# flowerfriend_rev6-nosma.net
KiCad netlist of a schematic drawn in EAGLE
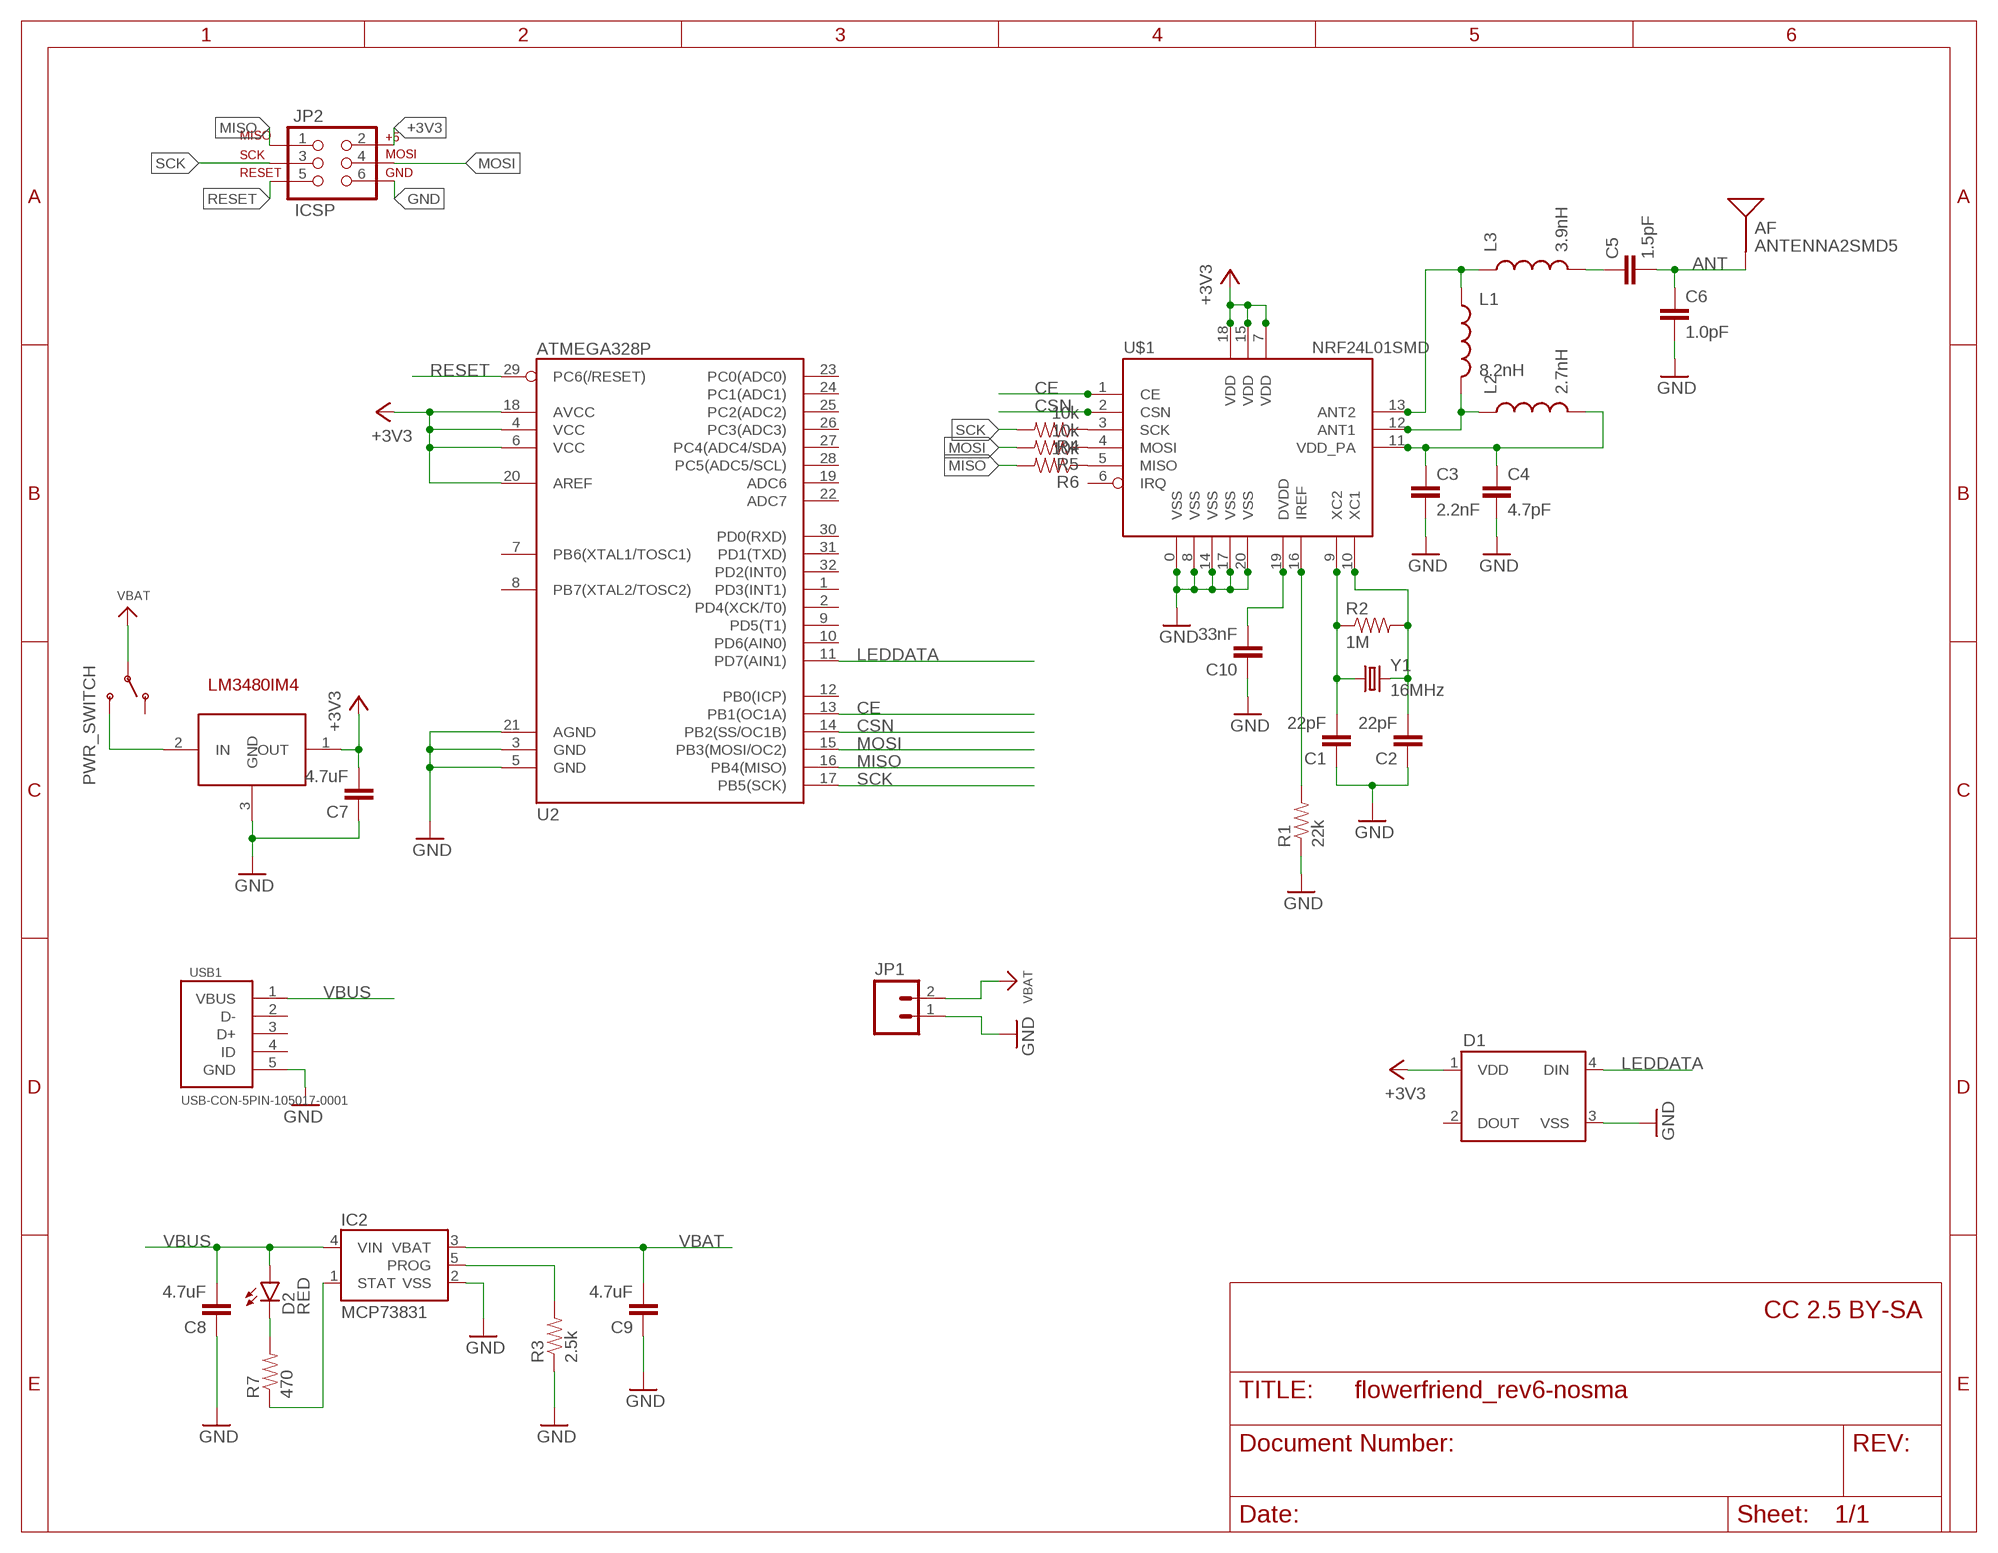
[diagram p0: schematic, sheet 1]

(export (version "E")
  (design (tool "Eeschema 10.0.6"))
  (components
    (comp (ref "AF")
      (value "ANTENNA2SMD5")
      (footprint "eagle-import:ANTENNA-CHIP5")
      (libsource (lib "eagle-import") (part "ANTENNA2SMD5"))
    )
    (comp (ref "C1")
      (value "22pF")
      (footprint "eagle-import:0805")
      (libsource (lib "eagle-import") (part "CAP0805"))
    )
    (comp (ref "C2")
      (value "22pF")
      (footprint "eagle-import:0805")
      (libsource (lib "eagle-import") (part "CAP0805"))
    )
    (comp (ref "C3")
      (value "2.2nF")
      (footprint "eagle-import:C0402")
      (libsource (lib "eagle-import") (part "CAP_C0402"))
    )
    (comp (ref "C4")
      (value "4.7pF")
      (footprint "eagle-import:C0402")
      (libsource (lib "eagle-import") (part "CAP_C0402"))
    )
    (comp (ref "C5")
      (value "1.5pF")
      (footprint "eagle-import:C0402")
      (libsource (lib "eagle-import") (part "CAP_C0402"))
    )
    (comp (ref "C6")
      (value "1.0pF")
      (footprint "eagle-import:C0402")
      (libsource (lib "eagle-import") (part "CAP_C0402"))
    )
    (comp (ref "C7")
      (value "4.7uF")
      (footprint "eagle-import:0805")
      (libsource (lib "eagle-import") (part "CAP0805"))
    )
    (comp (ref "C8")
      (value "4.7uF")
      (footprint "eagle-import:0805")
      (libsource (lib "eagle-import") (part "CAP0805"))
    )
    (comp (ref "C9")
      (value "4.7uF")
      (footprint "eagle-import:0805")
      (libsource (lib "eagle-import") (part "CAP0805"))
    )
    (comp (ref "C10")
      (value "33nF")
      (footprint "eagle-import:0805")
      (libsource (lib "eagle-import") (part "CAP0805"))
    )
    (comp (ref "D1")
      (value "WS2812B")
      (footprint "eagle-import:WS2812B")
      (libsource (lib "eagle-import") (part "WS2812B"))
    )
    (comp (ref "D2")
      (value "RED")
      (footprint "eagle-import:LED-0603")
      (libsource (lib "eagle-import") (part "LED-RED0603"))
    )
    (comp (ref "IC1")
      (value "LM3480IM4")
      (footprint "eagle-import:SOT23-3")
      (libsource (lib "eagle-import") (part "LM3480IM4"))
    )
    (comp (ref "IC2")
      (value "MCP73831")
      (footprint "eagle-import:SOT23-5")
      (libsource (lib "eagle-import") (part "MCP73831"))
    )
    (comp (ref "JP1")
      (value "M02PTH")
      (footprint "eagle-import:1X02")
      (libsource (lib "eagle-import") (part "M02PTH"))
    )
    (comp (ref "JP2")
      (value "ICSP")
      (footprint "eagle-import:2X3")
      (libsource (lib "eagle-import") (part "AVR_SPI_PRG_6PTH"))
    )
    (comp (ref "L1")
      (value "8.2nH")
      (footprint "eagle-import:C0402")
      (libsource (lib "eagle-import") (part "INDUCTOR0402"))
    )
    (comp (ref "L2")
      (value "2.7nH")
      (footprint "eagle-import:C0402")
      (libsource (lib "eagle-import") (part "INDUCTOR0402"))
    )
    (comp (ref "L3")
      (value "3.9nH")
      (footprint "eagle-import:C0402")
      (libsource (lib "eagle-import") (part "INDUCTOR0402"))
    )
    (comp (ref "PWR_SWITCH")
      (value "SWITCH_SPDT")
      (footprint "eagle-import:KPS-1290")
      (libsource (lib "eagle-import") (part "SWITCH_SPDT"))
    )
    (comp (ref "R1")
      (value "22k")
      (footprint "eagle-import:0805")
      (libsource (lib "eagle-import") (part "RESISTOR0805-RES"))
    )
    (comp (ref "R2")
      (value "1M")
      (footprint "eagle-import:0805")
      (libsource (lib "eagle-import") (part "RESISTOR0805-RES"))
    )
    (comp (ref "R3")
      (value "2.5k")
      (footprint "eagle-import:0805")
      (libsource (lib "eagle-import") (part "RESISTOR0805-RES"))
    )
    (comp (ref "R4")
      (value "10k")
      (footprint "eagle-import:0805")
      (libsource (lib "eagle-import") (part "RESISTOR0805-RES"))
    )
    (comp (ref "R5")
      (value "10k")
      (footprint "eagle-import:0805")
      (libsource (lib "eagle-import") (part "RESISTOR0805-RES"))
    )
    (comp (ref "R6")
      (value "10k")
      (footprint "eagle-import:0805")
      (libsource (lib "eagle-import") (part "RESISTOR0805-RES"))
    )
    (comp (ref "R7")
      (value "470")
      (footprint "eagle-import:0805")
      (libsource (lib "eagle-import") (part "RESISTOR0805-RES"))
    )
    (comp (ref "U$1")
      (value "NRF24L01SMD")
      (footprint "eagle-import:QFN20")
      (libsource (lib "eagle-import") (part "NRF24L01SMD"))
    )
    (comp (ref "U2")
      (value "ATMEGA328P")
      (footprint "eagle-import:TQFP32-08")
      (libsource (lib "eagle-import") (part "ATMEGA328_SMT"))
    )
    (comp (ref "USB1")
      (value "USB-CON-5PIN-105017-0001")
      (footprint "eagle-import:USB-MICRO-MOLEX-105017-0001")
      (libsource (lib "eagle-import") (part "USB-CON-5PIN-105017-0001"))
    )
    (comp (ref "Y1")
      (value "16MHz")
      (footprint "eagle-import:CRYSTAL-SMD-5X3")
      (libsource (lib "eagle-import") (part "CRYSTAL5X3"))
    )
  )
  (nets
    (net (code "1") (name "+3V3") (class "Default")
      (node (ref "C7") (pin "2") (pinfunction "2_2") (pintype "passive"))
      (node (ref "D1") (pin "1") (pinfunction "VDD_1") (pintype "power_in"))
      (node (ref "IC1") (pin "1") (pinfunction "OUT_1") (pintype "bidirectional"))
      (node (ref "JP2") (pin "2") (pinfunction "2_2") (pintype "passive"))
      (node (ref "U$1") (pin "15") (pinfunction "VDD_15") (pintype "power_in"))
      (node (ref "U$1") (pin "18") (pinfunction "VDD_18") (pintype "power_in"))
      (node (ref "U$1") (pin "7") (pinfunction "VDD_7") (pintype "power_in"))
      (node (ref "U2") (pin "18") (pinfunction "AVCC_18") (pintype "bidirectional"))
      (node (ref "U2") (pin "20") (pinfunction "AREF_20") (pintype "bidirectional"))
      (node (ref "U2") (pin "4") (pinfunction "VCC_4") (pintype "bidirectional"))
      (node (ref "U2") (pin "6") (pinfunction "VCC_6") (pintype "bidirectional"))
    )
    (net (code "2") (name "/ANT") (class "Default")
      (node (ref "AF") (pin "FEED") (pinfunction "SIGNAL_FEED") (pintype "bidirectional"))
      (node (ref "C5") (pin "2") (pinfunction "2_2") (pintype "passive"))
      (node (ref "C6") (pin "1") (pinfunction "1_1") (pintype "passive"))
    )
    (net (code "3") (name "/CE") (class "Default")
      (node (ref "U$1") (pin "1") (pinfunction "CE_1") (pintype "input"))
      (node (ref "U2") (pin "13") (pinfunction "PB1(OC1A)_13") (pintype "bidirectional"))
    )
    (net (code "4") (name "/CSN") (class "Default")
      (node (ref "U$1") (pin "2") (pinfunction "CSN_2") (pintype "input"))
      (node (ref "U2") (pin "14") (pinfunction "PB2(SS/OC1B)_14") (pintype "bidirectional"))
    )
    (net (code "5") (name "/LEDDATA") (class "Default")
      (node (ref "D1") (pin "4") (pinfunction "DIN_4") (pintype "input"))
      (node (ref "U2") (pin "11") (pinfunction "PD7(AIN1)_11") (pintype "bidirectional"))
    )
    (net (code "6") (name "/VBUS") (class "Default")
      (node (ref "C8") (pin "2") (pinfunction "2_2") (pintype "passive"))
      (node (ref "D2") (pin "A") (pinfunction "A_A") (pintype "passive"))
      (node (ref "IC2") (pin "4") (pinfunction "VIN_4") (pintype "power_in"))
      (node (ref "USB1") (pin "1") (pinfunction "VBUS_1") (pintype "power_in"))
    )
    (net (code "7") (name "GND") (class "Default")
      (node (ref "C1") (pin "1") (pinfunction "1_1") (pintype "passive"))
      (node (ref "C10") (pin "1") (pinfunction "1_1") (pintype "passive"))
      (node (ref "C2") (pin "1") (pinfunction "1_1") (pintype "passive"))
      (node (ref "C3") (pin "2") (pinfunction "2_2") (pintype "passive"))
      (node (ref "C4") (pin "2") (pinfunction "2_2") (pintype "passive"))
      (node (ref "C6") (pin "2") (pinfunction "2_2") (pintype "passive"))
      (node (ref "C7") (pin "1") (pinfunction "1_1") (pintype "passive"))
      (node (ref "C8") (pin "1") (pinfunction "1_1") (pintype "passive"))
      (node (ref "C9") (pin "1") (pinfunction "1_1") (pintype "passive"))
      (node (ref "D1") (pin "3") (pinfunction "VSS_3") (pintype "power_in"))
      (node (ref "IC1") (pin "3") (pinfunction "GND_3") (pintype "bidirectional"))
      (node (ref "IC2") (pin "2") (pinfunction "VSS_2") (pintype "power_in"))
      (node (ref "JP1") (pin "1") (pinfunction "1_1") (pintype "passive"))
      (node (ref "JP2") (pin "6") (pinfunction "6_6") (pintype "passive"))
      (node (ref "R1") (pin "1") (pinfunction "1_1") (pintype "passive"))
      (node (ref "R3") (pin "1") (pinfunction "1_1") (pintype "passive"))
      (node (ref "U$1") (pin "0") (pinfunction "VSS_0") (pintype "power_in"))
      (node (ref "U$1") (pin "14") (pinfunction "VSS_14") (pintype "power_in"))
      (node (ref "U$1") (pin "17") (pinfunction "VSS_17") (pintype "power_in"))
      (node (ref "U$1") (pin "20") (pinfunction "VSS_20") (pintype "power_in"))
      (node (ref "U$1") (pin "8") (pinfunction "VSS_8") (pintype "power_in"))
      (node (ref "U2") (pin "21") (pinfunction "AGND_21") (pintype "bidirectional"))
      (node (ref "U2") (pin "3") (pinfunction "GND_3") (pintype "bidirectional"))
      (node (ref "U2") (pin "5") (pinfunction "GND_5") (pintype "bidirectional"))
      (node (ref "USB1") (pin "5") (pinfunction "GND_5") (pintype "power_in"))
    )
    (net (code "8") (name "MISO") (class "Default")
      (node (ref "JP2") (pin "1") (pinfunction "1_1") (pintype "passive"))
      (node (ref "R6") (pin "2") (pinfunction "2_2") (pintype "passive"))
      (node (ref "U2") (pin "16") (pinfunction "PB4(MISO)_16") (pintype "bidirectional"))
    )
    (net (code "9") (name "MOSI") (class "Default")
      (node (ref "JP2") (pin "4") (pinfunction "4_4") (pintype "passive"))
      (node (ref "R5") (pin "2") (pinfunction "2_2") (pintype "passive"))
      (node (ref "U2") (pin "15") (pinfunction "PB3(MOSI/OC2)_15") (pintype "bidirectional"))
    )
    (net (code "10") (name "Net-(C5-Pad1)") (class "Default")
      (node (ref "C5") (pin "1") (pinfunction "1_1") (pintype "passive"))
      (node (ref "L3") (pin "2") (pinfunction "2_2") (pintype "passive"))
    )
    (net (code "11") (name "Net-(D2-PadC)") (class "Default")
      (node (ref "D2") (pin "C") (pinfunction "C_C") (pintype "passive"))
      (node (ref "R7") (pin "2") (pinfunction "2_2") (pintype "passive"))
    )
    (net (code "12") (name "Net-(IC1-IN)") (class "Default")
      (node (ref "IC1") (pin "2") (pinfunction "IN_2") (pintype "bidirectional"))
      (node (ref "PWR_SWITCH") (pin "S") (pinfunction "S_S") (pintype "passive"))
    )
    (net (code "13") (name "Net-(IC2-PROG)") (class "Default")
      (node (ref "IC2") (pin "5") (pinfunction "PROG_5") (pintype "input"))
      (node (ref "R3") (pin "2") (pinfunction "2_2") (pintype "passive"))
    )
    (net (code "14") (name "Net-(IC2-STAT)") (class "Default")
      (node (ref "IC2") (pin "1") (pinfunction "STAT_1") (pintype "output"))
      (node (ref "R7") (pin "1") (pinfunction "1_1") (pintype "passive"))
    )
    (net (code "15") (name "Net-(U$1-ANT1)") (class "Default")
      (node (ref "L1") (pin "2") (pinfunction "2_2") (pintype "passive"))
      (node (ref "L2") (pin "1") (pinfunction "1_1") (pintype "passive"))
      (node (ref "U$1") (pin "12") (pinfunction "ANT1_12") (pintype "output"))
    )
    (net (code "16") (name "Net-(U$1-ANT2)") (class "Default")
      (node (ref "L1") (pin "1") (pinfunction "1_1") (pintype "passive"))
      (node (ref "L3") (pin "1") (pinfunction "1_1") (pintype "passive"))
      (node (ref "U$1") (pin "13") (pinfunction "ANT2_13") (pintype "output"))
    )
    (net (code "17") (name "Net-(U$1-DVDD)") (class "Default")
      (node (ref "C10") (pin "2") (pinfunction "2_2") (pintype "passive"))
      (node (ref "U$1") (pin "19") (pinfunction "DVDD_19") (pintype "power_in"))
    )
    (net (code "18") (name "Net-(U$1-IREF)") (class "Default")
      (node (ref "R1") (pin "2") (pinfunction "2_2") (pintype "passive"))
      (node (ref "U$1") (pin "16") (pinfunction "IREF_16") (pintype "input"))
    )
    (net (code "19") (name "Net-(U$1-MISO)") (class "Default")
      (node (ref "R6") (pin "1") (pinfunction "1_1") (pintype "passive"))
      (node (ref "U$1") (pin "5") (pinfunction "MISO_5") (pintype "output"))
    )
    (net (code "20") (name "Net-(U$1-MOSI)") (class "Default")
      (node (ref "R5") (pin "1") (pinfunction "1_1") (pintype "passive"))
      (node (ref "U$1") (pin "4") (pinfunction "MOSI_4") (pintype "input"))
    )
    (net (code "21") (name "Net-(U$1-SCK)") (class "Default")
      (node (ref "R4") (pin "1") (pinfunction "1_1") (pintype "passive"))
      (node (ref "U$1") (pin "3") (pinfunction "SCK_3") (pintype "input"))
    )
    (net (code "22") (name "Net-(U$1-VDD_PA)") (class "Default")
      (node (ref "C3") (pin "1") (pinfunction "1_1") (pintype "passive"))
      (node (ref "C4") (pin "1") (pinfunction "1_1") (pintype "passive"))
      (node (ref "L2") (pin "2") (pinfunction "2_2") (pintype "passive"))
      (node (ref "U$1") (pin "11") (pinfunction "VDD_PA_11") (pintype "power_in"))
    )
    (net (code "23") (name "Net-(U$1-XC1)") (class "Default")
      (node (ref "C2") (pin "2") (pinfunction "2_2") (pintype "passive"))
      (node (ref "R2") (pin "2") (pinfunction "2_2") (pintype "passive"))
      (node (ref "U$1") (pin "10") (pinfunction "XC1_10") (pintype "input"))
      (node (ref "Y1") (pin "3") (pinfunction "2_3") (pintype "passive"))
    )
    (net (code "24") (name "Net-(U$1-XC2)") (class "Default")
      (node (ref "C1") (pin "2") (pinfunction "2_2") (pintype "passive"))
      (node (ref "R2") (pin "1") (pinfunction "1_1") (pintype "passive"))
      (node (ref "U$1") (pin "9") (pinfunction "XC2_9") (pintype "input"))
      (node (ref "Y1") (pin "1") (pinfunction "1_1") (pintype "passive"))
    )
    (net (code "25") (name "RESET") (class "Default")
      (node (ref "JP2") (pin "5") (pinfunction "5_5") (pintype "passive"))
      (node (ref "U2") (pin "29") (pinfunction "PC6(/RESET)_29") (pintype "bidirectional"))
    )
    (net (code "26") (name "SCK") (class "Default")
      (node (ref "JP2") (pin "3") (pinfunction "3_3") (pintype "passive"))
      (node (ref "R4") (pin "2") (pinfunction "2_2") (pintype "passive"))
      (node (ref "U2") (pin "17") (pinfunction "PB5(SCK)_17") (pintype "bidirectional"))
    )
    (net (code "27") (name "VBAT") (class "Default")
      (node (ref "C9") (pin "2") (pinfunction "2_2") (pintype "passive"))
      (node (ref "IC2") (pin "3") (pinfunction "VBAT_3") (pintype "power_in"))
      (node (ref "JP1") (pin "2") (pinfunction "2_2") (pintype "passive"))
      (node (ref "PWR_SWITCH") (pin "P") (pinfunction "P_P") (pintype "passive"))
    )
    (net (code "28") (name "unconnected-(D1-DOUT-Pad2)") (class "Default")
      (node (ref "D1") (pin "2") (pinfunction "DOUT_2") (pintype "output"))
    )
    (net (code "29") (name "unconnected-(PWR_SWITCH-PadO)") (class "Default")
      (node (ref "PWR_SWITCH") (pin "O") (pinfunction "O_O") (pintype "passive"))
    )
    (net (code "30") (name "unconnected-(U$1-IRQ-Pad6)") (class "Default")
      (node (ref "U$1") (pin "6") (pinfunction "IRQ_6") (pintype "output"))
    )
    (net (code "31") (name "unconnected-(U2-ADC6-Pad19)") (class "Default")
      (node (ref "U2") (pin "19") (pinfunction "ADC6_19") (pintype "bidirectional"))
    )
    (net (code "32") (name "unconnected-(U2-ADC7-Pad22)") (class "Default")
      (node (ref "U2") (pin "22") (pinfunction "ADC7_22") (pintype "bidirectional"))
    )
    (net (code "33") (name "unconnected-(U2-PB0(ICP)-Pad12)") (class "Default")
      (node (ref "U2") (pin "12") (pinfunction "PB0(ICP)_12") (pintype "bidirectional"))
    )
    (net (code "34") (name "unconnected-(U2-PB6(XTAL1{slash}TOSC1)-Pad7)") (class "Default")
      (node (ref "U2") (pin "7") (pinfunction "PB6(XTAL1/TOSC1)_7") (pintype "bidirectional"))
    )
    (net (code "35") (name "unconnected-(U2-PB7(XTAL2{slash}TOSC2)-Pad8)") (class "Default")
      (node (ref "U2") (pin "8") (pinfunction "PB7(XTAL2/TOSC2)_8") (pintype "bidirectional"))
    )
    (net (code "36") (name "unconnected-(U2-PC0(ADC0)-Pad23)") (class "Default")
      (node (ref "U2") (pin "23") (pinfunction "PC0(ADC0)_23") (pintype "bidirectional"))
    )
    (net (code "37") (name "unconnected-(U2-PC1(ADC1)-Pad24)") (class "Default")
      (node (ref "U2") (pin "24") (pinfunction "PC1(ADC1)_24") (pintype "bidirectional"))
    )
    (net (code "38") (name "unconnected-(U2-PC2(ADC2)-Pad25)") (class "Default")
      (node (ref "U2") (pin "25") (pinfunction "PC2(ADC2)_25") (pintype "bidirectional"))
    )
    (net (code "39") (name "unconnected-(U2-PC3(ADC3)-Pad26)") (class "Default")
      (node (ref "U2") (pin "26") (pinfunction "PC3(ADC3)_26") (pintype "bidirectional"))
    )
    (net (code "40") (name "unconnected-(U2-PC4(ADC4{slash}SDA)-Pad27)") (class "Default")
      (node (ref "U2") (pin "27") (pinfunction "PC4(ADC4/SDA)_27") (pintype "bidirectional"))
    )
    (net (code "41") (name "unconnected-(U2-PC5(ADC5{slash}SCL)-Pad28)") (class "Default")
      (node (ref "U2") (pin "28") (pinfunction "PC5(ADC5/SCL)_28") (pintype "bidirectional"))
    )
    (net (code "42") (name "unconnected-(U2-PD0(RXD)-Pad30)") (class "Default")
      (node (ref "U2") (pin "30") (pinfunction "PD0(RXD)_30") (pintype "bidirectional"))
    )
    (net (code "43") (name "unconnected-(U2-PD1(TXD)-Pad31)") (class "Default")
      (node (ref "U2") (pin "31") (pinfunction "PD1(TXD)_31") (pintype "bidirectional"))
    )
    (net (code "44") (name "unconnected-(U2-PD2(INT0)-Pad32)") (class "Default")
      (node (ref "U2") (pin "32") (pinfunction "PD2(INT0)_32") (pintype "bidirectional"))
    )
    (net (code "45") (name "unconnected-(U2-PD3(INT1)-Pad1)") (class "Default")
      (node (ref "U2") (pin "1") (pinfunction "PD3(INT1)_1") (pintype "bidirectional"))
    )
    (net (code "46") (name "unconnected-(U2-PD4(XCK{slash}T0)-Pad2)") (class "Default")
      (node (ref "U2") (pin "2") (pinfunction "PD4(XCK/T0)_2") (pintype "bidirectional"))
    )
    (net (code "47") (name "unconnected-(U2-PD5(T1)-Pad9)") (class "Default")
      (node (ref "U2") (pin "9") (pinfunction "PD5(T1)_9") (pintype "bidirectional"))
    )
    (net (code "48") (name "unconnected-(U2-PD6(AIN0)-Pad10)") (class "Default")
      (node (ref "U2") (pin "10") (pinfunction "PD6(AIN0)_10") (pintype "bidirectional"))
    )
    (net (code "49") (name "unconnected-(USB1-D+-Pad3)") (class "Default")
      (node (ref "USB1") (pin "3") (pinfunction "D+_3") (pintype "bidirectional"))
    )
    (net (code "50") (name "unconnected-(USB1-D--Pad2)") (class "Default")
      (node (ref "USB1") (pin "2") (pinfunction "D-_2") (pintype "bidirectional"))
    )
    (net (code "51") (name "unconnected-(USB1-ID-Pad4)") (class "Default")
      (node (ref "USB1") (pin "4") (pinfunction "ID_4") (pintype "bidirectional"))
    )
  )
)
